# SimpleTimerPCB.net
KiCad netlist of a schematic drawn in EAGLE
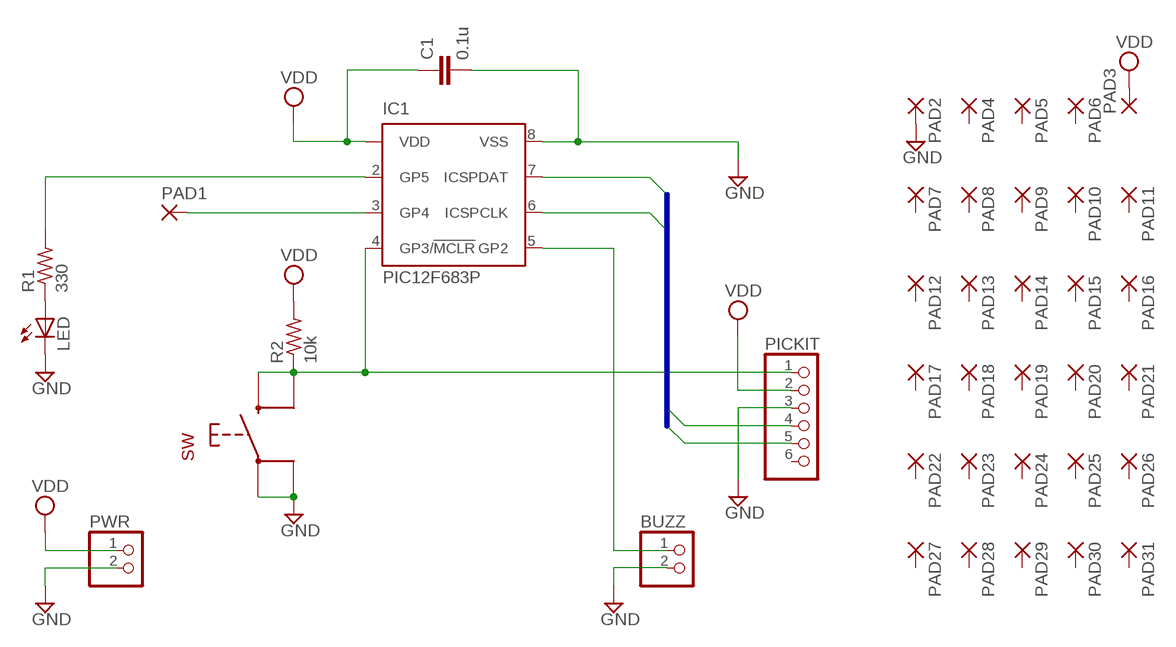
[diagram p0: schematic, sheet 1]

(export (version "E")
  (design (tool "Eeschema 10.0.6"))
  (components
    (comp (ref "BUZZ")
      (value "PINHD-1X2")
      (footprint "eagle-import:1X02")
      (libsource (lib "eagle-import") (part "PINHD-1X2"))
    )
    (comp (ref "C1")
      (value "0.1u")
      (footprint "eagle-import:C050-024X044")
      (libsource (lib "eagle-import") (part "C-EU050-024X044"))
    )
    (comp (ref "IC1")
      (value "PIC12F683P")
      (footprint "eagle-import:DIL8")
      (fields (field (name "MF") "MICROCHIP") (field (name "MPN") "PIC12F683-I/P"))
      (libsource (lib "eagle-import") (part "PIC12F683P"))
    )
    (comp (ref "LED")
      (value "LED3MM")
      (footprint "eagle-import:LED3MM")
      (libsource (lib "eagle-import") (part "LED3MM"))
    )
    (comp (ref "PAD1")
      (value "1,6/0,9")
      (footprint "eagle-import:1,6_0,9")
      (libsource (lib "eagle-import") (part "1,6/0,9"))
    )
    (comp (ref "PAD2")
      (value "1,6/0,9")
      (footprint "eagle-import:1,6_0,9")
      (libsource (lib "eagle-import") (part "1,6/0,9"))
    )
    (comp (ref "PAD3")
      (value "1,6/0,9")
      (footprint "eagle-import:1,6_0,9")
      (libsource (lib "eagle-import") (part "1,6/0,9"))
    )
    (comp (ref "PAD4")
      (value "1,6/0,9")
      (footprint "eagle-import:1,6_0,9")
      (libsource (lib "eagle-import") (part "1,6/0,9"))
    )
    (comp (ref "PAD5")
      (value "1,6/0,9")
      (footprint "eagle-import:1,6_0,9")
      (libsource (lib "eagle-import") (part "1,6/0,9"))
    )
    (comp (ref "PAD6")
      (value "1,6/0,9")
      (footprint "eagle-import:1,6_0,9")
      (libsource (lib "eagle-import") (part "1,6/0,9"))
    )
    (comp (ref "PAD7")
      (value "1,6/0,9")
      (footprint "eagle-import:1,6_0,9")
      (libsource (lib "eagle-import") (part "1,6/0,9"))
    )
    (comp (ref "PAD8")
      (value "1,6/0,9")
      (footprint "eagle-import:1,6_0,9")
      (libsource (lib "eagle-import") (part "1,6/0,9"))
    )
    (comp (ref "PAD9")
      (value "1,6/0,9")
      (footprint "eagle-import:1,6_0,9")
      (libsource (lib "eagle-import") (part "1,6/0,9"))
    )
    (comp (ref "PAD10")
      (value "1,6/0,9")
      (footprint "eagle-import:1,6_0,9")
      (libsource (lib "eagle-import") (part "1,6/0,9"))
    )
    (comp (ref "PAD11")
      (value "1,6/0,9")
      (footprint "eagle-import:1,6_0,9")
      (libsource (lib "eagle-import") (part "1,6/0,9"))
    )
    (comp (ref "PAD12")
      (value "1,6/0,9")
      (footprint "eagle-import:1,6_0,9")
      (libsource (lib "eagle-import") (part "1,6/0,9"))
    )
    (comp (ref "PAD13")
      (value "1,6/0,9")
      (footprint "eagle-import:1,6_0,9")
      (libsource (lib "eagle-import") (part "1,6/0,9"))
    )
    (comp (ref "PAD14")
      (value "1,6/0,9")
      (footprint "eagle-import:1,6_0,9")
      (libsource (lib "eagle-import") (part "1,6/0,9"))
    )
    (comp (ref "PAD15")
      (value "1,6/0,9")
      (footprint "eagle-import:1,6_0,9")
      (libsource (lib "eagle-import") (part "1,6/0,9"))
    )
    (comp (ref "PAD16")
      (value "1,6/0,9")
      (footprint "eagle-import:1,6_0,9")
      (libsource (lib "eagle-import") (part "1,6/0,9"))
    )
    (comp (ref "PAD17")
      (value "1,6/0,9")
      (footprint "eagle-import:1,6_0,9")
      (libsource (lib "eagle-import") (part "1,6/0,9"))
    )
    (comp (ref "PAD18")
      (value "1,6/0,9")
      (footprint "eagle-import:1,6_0,9")
      (libsource (lib "eagle-import") (part "1,6/0,9"))
    )
    (comp (ref "PAD19")
      (value "1,6/0,9")
      (footprint "eagle-import:1,6_0,9")
      (libsource (lib "eagle-import") (part "1,6/0,9"))
    )
    (comp (ref "PAD20")
      (value "1,6/0,9")
      (footprint "eagle-import:1,6_0,9")
      (libsource (lib "eagle-import") (part "1,6/0,9"))
    )
    (comp (ref "PAD21")
      (value "1,6/0,9")
      (footprint "eagle-import:1,6_0,9")
      (libsource (lib "eagle-import") (part "1,6/0,9"))
    )
    (comp (ref "PAD22")
      (value "1,6/0,9")
      (footprint "eagle-import:1,6_0,9")
      (libsource (lib "eagle-import") (part "1,6/0,9"))
    )
    (comp (ref "PAD23")
      (value "1,6/0,9")
      (footprint "eagle-import:1,6_0,9")
      (libsource (lib "eagle-import") (part "1,6/0,9"))
    )
    (comp (ref "PAD24")
      (value "1,6/0,9")
      (footprint "eagle-import:1,6_0,9")
      (libsource (lib "eagle-import") (part "1,6/0,9"))
    )
    (comp (ref "PAD25")
      (value "1,6/0,9")
      (footprint "eagle-import:1,6_0,9")
      (libsource (lib "eagle-import") (part "1,6/0,9"))
    )
    (comp (ref "PAD26")
      (value "1,6/0,9")
      (footprint "eagle-import:1,6_0,9")
      (libsource (lib "eagle-import") (part "1,6/0,9"))
    )
    (comp (ref "PAD27")
      (value "1,6/0,9")
      (footprint "eagle-import:1,6_0,9")
      (libsource (lib "eagle-import") (part "1,6/0,9"))
    )
    (comp (ref "PAD28")
      (value "1,6/0,9")
      (footprint "eagle-import:1,6_0,9")
      (libsource (lib "eagle-import") (part "1,6/0,9"))
    )
    (comp (ref "PAD29")
      (value "1,6/0,9")
      (footprint "eagle-import:1,6_0,9")
      (libsource (lib "eagle-import") (part "1,6/0,9"))
    )
    (comp (ref "PAD30")
      (value "1,6/0,9")
      (footprint "eagle-import:1,6_0,9")
      (libsource (lib "eagle-import") (part "1,6/0,9"))
    )
    (comp (ref "PAD31")
      (value "1,6/0,9")
      (footprint "eagle-import:1,6_0,9")
      (libsource (lib "eagle-import") (part "1,6/0,9"))
    )
    (comp (ref "PICKIT")
      (value "PINHD-1X6")
      (footprint "eagle-import:1X06")
      (libsource (lib "eagle-import") (part "PINHD-1X6"))
    )
    (comp (ref "PWR")
      (value "PINHD-1X2")
      (footprint "eagle-import:1X02")
      (libsource (lib "eagle-import") (part "PINHD-1X2"))
    )
    (comp (ref "R1")
      (value "330")
      (footprint "eagle-import:0204_7")
      (libsource (lib "eagle-import") (part "R-US_0204/7"))
    )
    (comp (ref "R2")
      (value "10k")
      (footprint "eagle-import:0204_7")
      (libsource (lib "eagle-import") (part "R-US_0204/7"))
    )
    (comp (ref "SW")
      (value "TACT-SWITCH")
      (footprint "eagle-import:TACTSW-25X20")
      (libsource (lib "eagle-import") (part "TACT-SWITCH"))
    )
  )
  (nets
    (net (code "1") (name "/PIN4") (class "Default")
      (node (ref "IC1") (pin "7") (pinfunction "ICSPDAT_7") (pintype "bidirectional"))
      (node (ref "PICKIT") (pin "4") (pinfunction "4_4") (pintype "passive"))
    )
    (net (code "2") (name "/PIN5") (class "Default")
      (node (ref "IC1") (pin "6") (pinfunction "ICSPCLK_6") (pintype "bidirectional"))
      (node (ref "PICKIT") (pin "5") (pinfunction "5_5") (pintype "passive"))
    )
    (net (code "3") (name "GND") (class "Default")
      (node (ref "BUZZ") (pin "2") (pinfunction "2_2") (pintype "passive"))
      (node (ref "C1") (pin "2") (pinfunction "2_2") (pintype "passive"))
      (node (ref "IC1") (pin "8") (pinfunction "VSS_8") (pintype "power_in"))
      (node (ref "LED") (pin "K") (pinfunction "C_K") (pintype "passive"))
      (node (ref "PAD2") (pin "1") (pinfunction "P_1") (pintype "passive"))
      (node (ref "PICKIT") (pin "3") (pinfunction "3_3") (pintype "passive"))
      (node (ref "PWR") (pin "2") (pinfunction "2_2") (pintype "passive"))
      (node (ref "SW") (pin "3") (pinfunction "P1_3") (pintype "passive"))
      (node (ref "SW") (pin "4") (pinfunction "P2_4") (pintype "passive"))
    )
    (net (code "4") (name "Net-(IC1-GP2)") (class "Default")
      (node (ref "BUZZ") (pin "1") (pinfunction "1_1") (pintype "passive"))
      (node (ref "IC1") (pin "5") (pinfunction "GP2_5") (pintype "bidirectional"))
    )
    (net (code "5") (name "Net-(IC1-GP3{slash}~{MCLR})") (class "Default")
      (node (ref "IC1") (pin "4") (pinfunction "GP3/~{MCLR}_4") (pintype "bidirectional"))
      (node (ref "PICKIT") (pin "1") (pinfunction "1_1") (pintype "passive"))
      (node (ref "R2") (pin "1") (pinfunction "1_1") (pintype "passive"))
      (node (ref "SW") (pin "1") (pinfunction "S1_1") (pintype "passive"))
      (node (ref "SW") (pin "2") (pinfunction "S2_2") (pintype "passive"))
    )
    (net (code "6") (name "Net-(IC1-GP4)") (class "Default")
      (node (ref "IC1") (pin "3") (pinfunction "GP4_3") (pintype "bidirectional"))
      (node (ref "PAD1") (pin "1") (pinfunction "P_1") (pintype "passive"))
    )
    (net (code "7") (name "Net-(IC1-GP5)") (class "Default")
      (node (ref "IC1") (pin "2") (pinfunction "GP5_2") (pintype "bidirectional"))
      (node (ref "R1") (pin "2") (pinfunction "2_2") (pintype "passive"))
    )
    (net (code "8") (name "Net-(LED-PadA)") (class "Default")
      (node (ref "LED") (pin "A") (pinfunction "A_A") (pintype "passive"))
      (node (ref "R1") (pin "1") (pinfunction "1_1") (pintype "passive"))
    )
    (net (code "9") (name "VDD") (class "Default")
      (node (ref "C1") (pin "1") (pinfunction "1_1") (pintype "passive"))
      (node (ref "IC1") (pin "1") (pinfunction "VDD_1") (pintype "power_in"))
      (node (ref "PAD3") (pin "1") (pinfunction "P_1") (pintype "passive"))
      (node (ref "PICKIT") (pin "2") (pinfunction "2_2") (pintype "passive"))
      (node (ref "PWR") (pin "1") (pinfunction "1_1") (pintype "passive"))
      (node (ref "R2") (pin "2") (pinfunction "2_2") (pintype "passive"))
    )
    (net (code "10") (name "unconnected-(PAD4-P-Pad1)") (class "Default")
      (node (ref "PAD4") (pin "1") (pinfunction "P_1") (pintype "passive"))
    )
    (net (code "11") (name "unconnected-(PAD5-P-Pad1)") (class "Default")
      (node (ref "PAD5") (pin "1") (pinfunction "P_1") (pintype "passive"))
    )
    (net (code "12") (name "unconnected-(PAD6-P-Pad1)") (class "Default")
      (node (ref "PAD6") (pin "1") (pinfunction "P_1") (pintype "passive"))
    )
    (net (code "13") (name "unconnected-(PAD7-P-Pad1)") (class "Default")
      (node (ref "PAD7") (pin "1") (pinfunction "P_1") (pintype "passive"))
    )
    (net (code "14") (name "unconnected-(PAD8-P-Pad1)") (class "Default")
      (node (ref "PAD8") (pin "1") (pinfunction "P_1") (pintype "passive"))
    )
    (net (code "15") (name "unconnected-(PAD9-P-Pad1)") (class "Default")
      (node (ref "PAD9") (pin "1") (pinfunction "P_1") (pintype "passive"))
    )
    (net (code "16") (name "unconnected-(PAD10-P-Pad1)") (class "Default")
      (node (ref "PAD10") (pin "1") (pinfunction "P_1") (pintype "passive"))
    )
    (net (code "17") (name "unconnected-(PAD11-P-Pad1)") (class "Default")
      (node (ref "PAD11") (pin "1") (pinfunction "P_1") (pintype "passive"))
    )
    (net (code "18") (name "unconnected-(PAD12-P-Pad1)") (class "Default")
      (node (ref "PAD12") (pin "1") (pinfunction "P_1") (pintype "passive"))
    )
    (net (code "19") (name "unconnected-(PAD13-P-Pad1)") (class "Default")
      (node (ref "PAD13") (pin "1") (pinfunction "P_1") (pintype "passive"))
    )
    (net (code "20") (name "unconnected-(PAD14-P-Pad1)") (class "Default")
      (node (ref "PAD14") (pin "1") (pinfunction "P_1") (pintype "passive"))
    )
    (net (code "21") (name "unconnected-(PAD15-P-Pad1)") (class "Default")
      (node (ref "PAD15") (pin "1") (pinfunction "P_1") (pintype "passive"))
    )
    (net (code "22") (name "unconnected-(PAD16-P-Pad1)") (class "Default")
      (node (ref "PAD16") (pin "1") (pinfunction "P_1") (pintype "passive"))
    )
    (net (code "23") (name "unconnected-(PAD17-P-Pad1)") (class "Default")
      (node (ref "PAD17") (pin "1") (pinfunction "P_1") (pintype "passive"))
    )
    (net (code "24") (name "unconnected-(PAD18-P-Pad1)") (class "Default")
      (node (ref "PAD18") (pin "1") (pinfunction "P_1") (pintype "passive"))
    )
    (net (code "25") (name "unconnected-(PAD19-P-Pad1)") (class "Default")
      (node (ref "PAD19") (pin "1") (pinfunction "P_1") (pintype "passive"))
    )
    (net (code "26") (name "unconnected-(PAD20-P-Pad1)") (class "Default")
      (node (ref "PAD20") (pin "1") (pinfunction "P_1") (pintype "passive"))
    )
    (net (code "27") (name "unconnected-(PAD21-P-Pad1)") (class "Default")
      (node (ref "PAD21") (pin "1") (pinfunction "P_1") (pintype "passive"))
    )
    (net (code "28") (name "unconnected-(PAD22-P-Pad1)") (class "Default")
      (node (ref "PAD22") (pin "1") (pinfunction "P_1") (pintype "passive"))
    )
    (net (code "29") (name "unconnected-(PAD23-P-Pad1)") (class "Default")
      (node (ref "PAD23") (pin "1") (pinfunction "P_1") (pintype "passive"))
    )
    (net (code "30") (name "unconnected-(PAD24-P-Pad1)") (class "Default")
      (node (ref "PAD24") (pin "1") (pinfunction "P_1") (pintype "passive"))
    )
    (net (code "31") (name "unconnected-(PAD25-P-Pad1)") (class "Default")
      (node (ref "PAD25") (pin "1") (pinfunction "P_1") (pintype "passive"))
    )
    (net (code "32") (name "unconnected-(PAD26-P-Pad1)") (class "Default")
      (node (ref "PAD26") (pin "1") (pinfunction "P_1") (pintype "passive"))
    )
    (net (code "33") (name "unconnected-(PAD27-P-Pad1)") (class "Default")
      (node (ref "PAD27") (pin "1") (pinfunction "P_1") (pintype "passive"))
    )
    (net (code "34") (name "unconnected-(PAD28-P-Pad1)") (class "Default")
      (node (ref "PAD28") (pin "1") (pinfunction "P_1") (pintype "passive"))
    )
    (net (code "35") (name "unconnected-(PAD29-P-Pad1)") (class "Default")
      (node (ref "PAD29") (pin "1") (pinfunction "P_1") (pintype "passive"))
    )
    (net (code "36") (name "unconnected-(PAD30-P-Pad1)") (class "Default")
      (node (ref "PAD30") (pin "1") (pinfunction "P_1") (pintype "passive"))
    )
    (net (code "37") (name "unconnected-(PAD31-P-Pad1)") (class "Default")
      (node (ref "PAD31") (pin "1") (pinfunction "P_1") (pintype "passive"))
    )
    (net (code "38") (name "unconnected-(PICKIT-Pad6)") (class "Default")
      (node (ref "PICKIT") (pin "6") (pinfunction "6_6") (pintype "passive"))
    )
  )
)
